# fpga_misc.net
KiCad netlist of a schematic drawn in Altium Designer
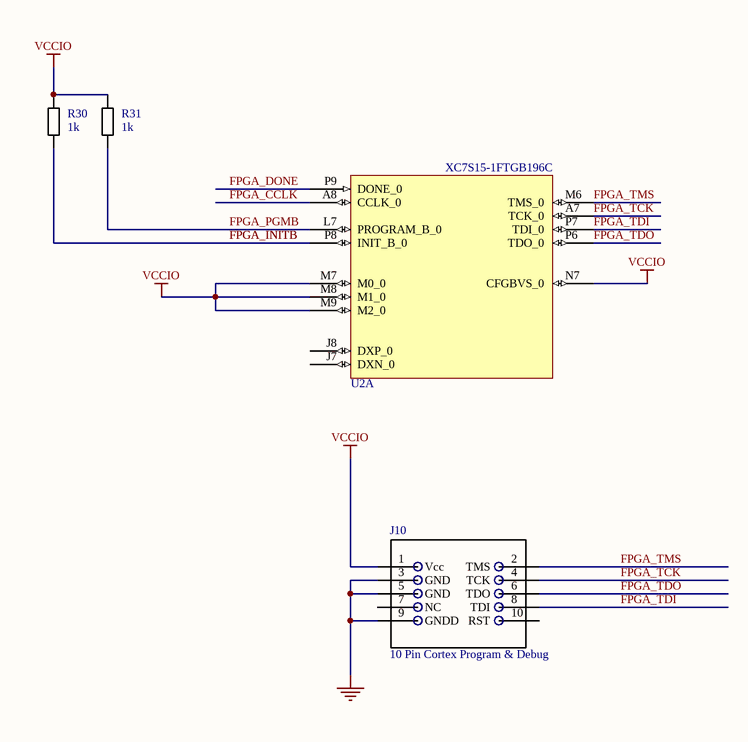
[diagram p0: fpga_misc.SchDoc]

(export (version "E")
  (design (tool "Eeschema 10.0.6"))
  (components
    (comp (ref "J10")
      (value "10 Pin Cortex Program & Debug")
      (footprint "0.5mm_SMD_Header_5x2")
      (description "10 Pin Cortex Program & Debug 0.5mm pitch")
      (fields (field (name "PART NUMBER") "Cortex_Debug_Header_10Pin"))
      (libsource (lib "NewAE_AltiumLib") (part "Cortex_Debug_Header_10Pin"))
    )
    (comp (ref "R30")
      (value "1k")
      (footprint "RESC1608X55N")
      (description "1k res, 0603, 1%, 1/10W")
      (fields (field (name "PART NUMBER") "RCHIP-1K-0603") (field (name "TOLERANCE") "1%"))
      (libsource (lib "NewAE_AltiumLib") (part "RES-EU"))
    )
    (comp (ref "R31")
      (value "1k")
      (footprint "RESC1608X55N")
      (description "1k res, 0603, 1%, 1/10W")
      (fields (field (name "PART NUMBER") "RCHIP-1K-0603") (field (name "TOLERANCE") "1%"))
      (libsource (lib "NewAE_AltiumLib") (part "RES-EU"))
    )
    (comp (ref "U2")
      (value "XC7S15-1FTGB196C")
      (footprint "BGA_FTGB196")
      (description "Xilinx Spartan 7 FPGA, 196FTGB")
      (libsource (lib "NewAE_AltiumLib") (part "XC7S6FTGB196"))
    )
  )
  (nets
    (net (code "1") (name "/FPGA_CCLK") (class "Default")
      (node (ref "U2") (pin "A8") (pinfunction "CCLK_0_A8") (pintype "bidirectional"))
    )
    (net (code "2") (name "/FPGA_DONE") (class "Default")
      (node (ref "U2") (pin "P9") (pinfunction "DONE_0_P9") (pintype "input"))
    )
    (net (code "3") (name "/FPGA_INITB") (class "Default")
      (node (ref "R30") (pin "2") (pinfunction "2_2") (pintype "passive"))
      (node (ref "U2") (pin "P8") (pinfunction "INIT_B_0_P8") (pintype "bidirectional"))
    )
    (net (code "4") (name "/FPGA_PGMB") (class "Default")
      (node (ref "R31") (pin "2") (pinfunction "2_2") (pintype "passive"))
      (node (ref "U2") (pin "L7") (pinfunction "PROGRAM_B_0_L7") (pintype "bidirectional"))
    )
    (net (code "5") (name "/FPGA_TCK") (class "Default")
      (node (ref "J10") (pin "4") (pinfunction "TCK_4") (pintype "passive"))
      (node (ref "U2") (pin "A7") (pinfunction "TCK_0_A7") (pintype "bidirectional"))
    )
    (net (code "6") (name "/FPGA_TDI") (class "Default")
      (node (ref "J10") (pin "8") (pinfunction "TDI_8") (pintype "passive"))
      (node (ref "U2") (pin "P7") (pinfunction "TDI_0_P7") (pintype "bidirectional"))
    )
    (net (code "7") (name "/FPGA_TDO") (class "Default")
      (node (ref "J10") (pin "6") (pinfunction "TDO_6") (pintype "passive"))
      (node (ref "U2") (pin "P6") (pinfunction "TDO_0_P6") (pintype "bidirectional"))
    )
    (net (code "8") (name "/FPGA_TMS") (class "Default")
      (node (ref "J10") (pin "2") (pinfunction "TMS_2") (pintype "passive"))
      (node (ref "U2") (pin "M6") (pinfunction "TMS_0_M6") (pintype "bidirectional"))
    )
    (net (code "9") (name "GND") (class "Default")
      (node (ref "J10") (pin "3") (pinfunction "GND_3") (pintype "passive"))
      (node (ref "J10") (pin "5") (pinfunction "GND_5") (pintype "passive"))
      (node (ref "J10") (pin "9") (pinfunction "GNDD_9") (pintype "passive"))
    )
    (net (code "10") (name "VCCIO") (class "Default")
      (node (ref "J10") (pin "1") (pinfunction "Vcc_1") (pintype "passive"))
      (node (ref "R30") (pin "1") (pinfunction "1_1") (pintype "passive"))
      (node (ref "R31") (pin "1") (pinfunction "1_1") (pintype "passive"))
      (node (ref "U2") (pin "M7") (pinfunction "M0_0_M7") (pintype "bidirectional"))
      (node (ref "U2") (pin "M8") (pinfunction "M1_0_M8") (pintype "bidirectional"))
      (node (ref "U2") (pin "M9") (pinfunction "M2_0_M9") (pintype "bidirectional"))
      (node (ref "U2") (pin "N7") (pinfunction "CFGBVS_0_N7") (pintype "bidirectional"))
    )
    (net (code "11") (name "unconnected-(J10-NC-Pad7)") (class "Default")
      (node (ref "J10") (pin "7") (pinfunction "NC_7") (pintype "passive"))
    )
    (net (code "12") (name "unconnected-(J10-RST-Pad10)") (class "Default")
      (node (ref "J10") (pin "10") (pinfunction "RST_10") (pintype "passive"))
    )
    (net (code "13") (name "unconnected-(U2A-DXN_0-PadJ7)") (class "Default")
      (node (ref "U2") (pin "J7") (pinfunction "DXN_0_J7") (pintype "bidirectional"))
    )
    (net (code "14") (name "unconnected-(U2A-DXP_0-PadJ8)") (class "Default")
      (node (ref "U2") (pin "J8") (pinfunction "DXP_0_J8") (pintype "bidirectional"))
    )
  )
)
